# SUPERPID.net
KiCad netlist of a schematic drawn in Altium Designer
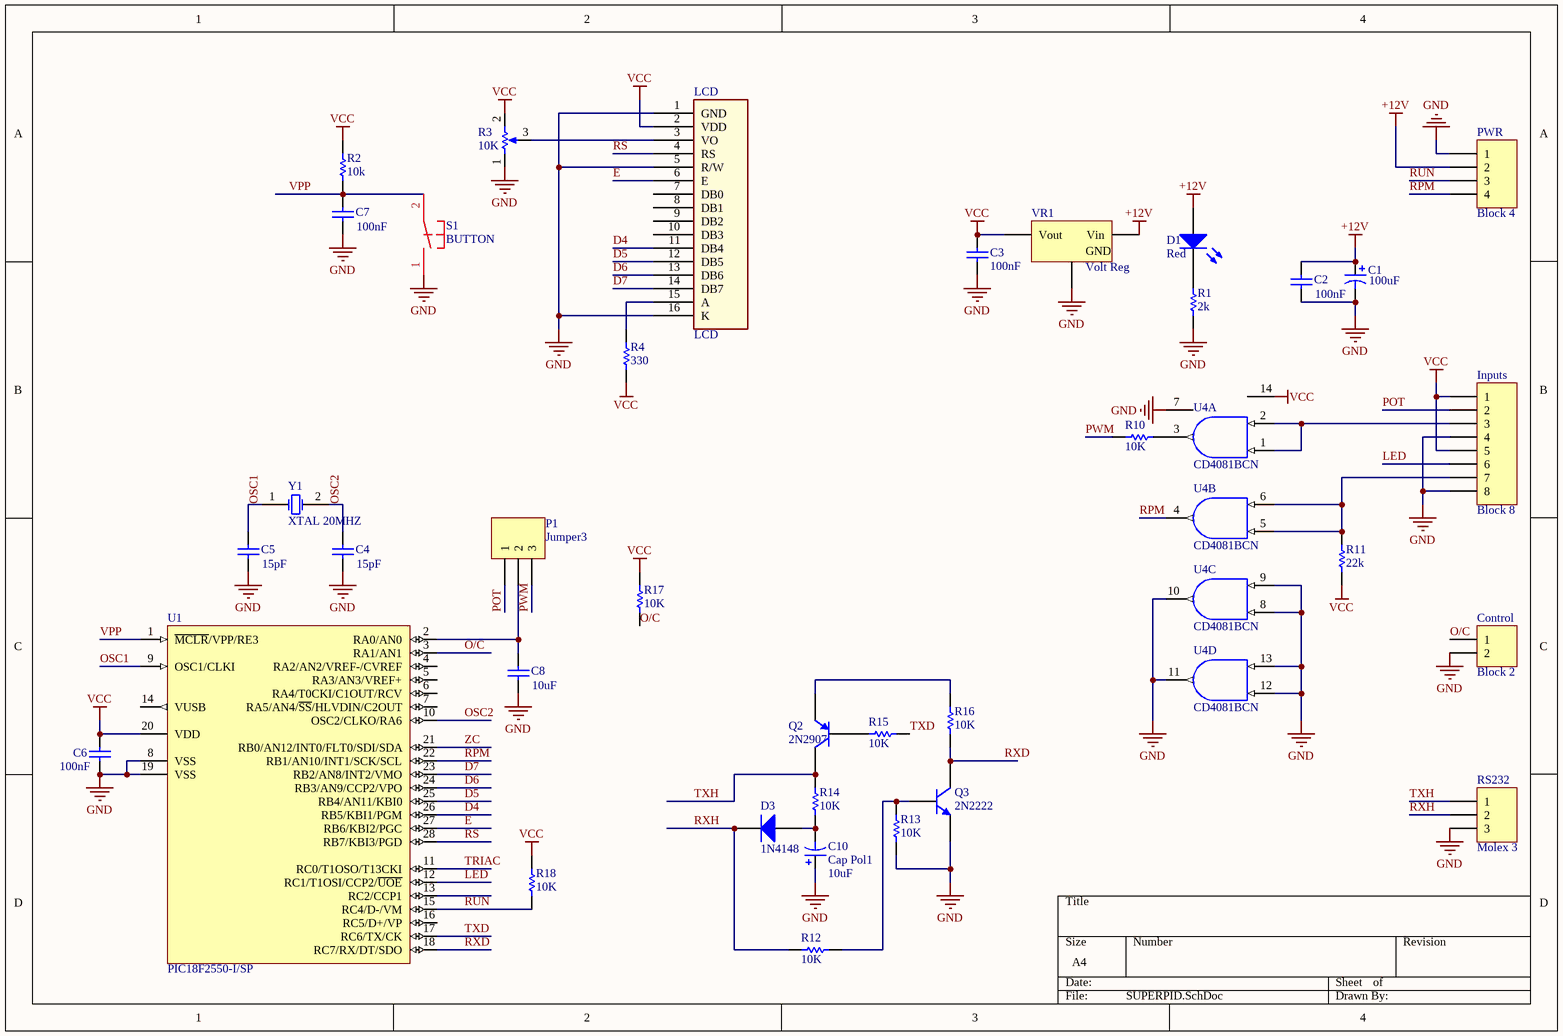
[diagram p0: SUPERPID.SchDoc]

(export (version "E")
  (design (tool "Eeschema 10.0.6"))
  (components
    (comp (ref "C1")
      (value "100uF")
      (footprint "RADIAL CAPACITOR - 100uF - 10V")
      (description "Polarized Capacitor (Radial)")
      (fields (field (name "PUBLISHER") "Altium Limited"))
      (libsource (lib "Miscellaneous Devices") (part "Cap Pol1"))
    )
    (comp (ref "C2")
      (value "100nF")
      (footprint "6-0805_N")
      (description "Capacitor 0805")
      (fields (field (name "PUBLISHER") "Altium Limited"))
      (libsource (lib "Miscellaneous Devices") (part "Cap Semi"))
    )
    (comp (ref "C3")
      (value "100nF")
      (footprint "6-0805_N")
      (description "Capacitor 0805")
      (fields (field (name "PUBLISHER") "Altium Limited"))
      (libsource (lib "Miscellaneous Devices") (part "Cap Semi"))
    )
    (comp (ref "C4")
      (value "15pF")
      (footprint "6-0805_N")
      (description "Capacitor 0805")
      (fields (field (name "PUBLISHER") "Altium Limited"))
      (libsource (lib "Miscellaneous Devices") (part "Cap Semi"))
    )
    (comp (ref "C5")
      (value "15pF")
      (footprint "6-0805_N")
      (description "Capacitor 0805")
      (fields (field (name "PUBLISHER") "Altium Limited"))
      (libsource (lib "Miscellaneous Devices") (part "Cap Semi"))
    )
    (comp (ref "C6")
      (value "100nF")
      (footprint "6-0805_N")
      (description "Capacitor 0805")
      (fields (field (name "PUBLISHER") "Altium Limited"))
      (libsource (lib "Miscellaneous Devices") (part "Cap Semi"))
    )
    (comp (ref "C7")
      (value "100nF")
      (footprint "6-0805_N")
      (description "Capacitor 0805")
      (fields (field (name "PUBLISHER") "Altium Limited"))
      (libsource (lib "Miscellaneous Devices") (part "Cap Semi"))
    )
    (comp (ref "C8")
      (value "10uF")
      (footprint "CC3216-1206")
      (description "Capacitor 0805")
      (fields (field (name "PUBLISHER") "Altium Limited"))
      (libsource (lib "Miscellaneous Devices") (part "Cap Semi"))
    )
    (comp (ref "C10")
      (value "Cap Pol1")
      (footprint "CONDENSADOR SMT")
      (description "Polarized Capacitor (Radial)")
      (fields (field (name "ALTIUM_VALUE") "10uF"))
      (libsource (lib "Miscellaneous Devices") (part "Cap Pol1"))
    )
    (comp (ref "Control")
      (value "Block 2")
      (footprint "BOR-2")
      (description "Header, 2-Pin")
      (fields (field (name "PUBLISHER") "Altium Limited"))
      (libsource (lib "Miscellaneous Connectors") (part "Header 2"))
    )
    (comp (ref "D1")
      (value "Red")
      (footprint "0805 LED RED")
      (description "Typical BLUE SiC LED")
      (fields (field (name "PUBLISHER") "Altium Limited"))
      (libsource (lib "Miscellaneous Devices") (part "LED3"))
    )
    (comp (ref "D3")
      (value "1N4148")
      (footprint "Diodo")
      (description "1 Amp General Purpose Rectifier")
      (fields (field (name "PUBLISHER") "Altium Limited"))
      (libsource (lib "Miscellaneous Devices") (part "Diode 1N4007"))
    )
    (comp (ref "Inputs")
      (value "Block 8")
      (footprint "BOR-8-5.08")
      (description "Header, 8-Pin")
      (fields (field (name "PUBLISHER") "Altium Limited"))
      (libsource (lib "Miscellaneous Connectors") (part "Header 8"))
    )
    (comp (ref "LCD")
      (value "LCD")
      (footprint "LCD 16x2")
      (description "HD44780 parallel interface chipset")
      (libsource (lib "ESQUEMATICOS") (part "LCD 16*2"))
    )
    (comp (ref "P1")
      (value "Jumper3")
      (footprint "HDR1X3")
      (description "Header, 3-Pin")
      (fields (field (name "PUBLISHER") "Altium Limited"))
      (libsource (lib "Miscellaneous Connectors") (part "Header 3"))
    )
    (comp (ref "PWR")
      (value "Block 4")
      (footprint "BOR-4-5.08")
      (description "Header, 4-Pin")
      (fields (field (name "PUBLISHER") "Altium Limited"))
      (libsource (lib "Miscellaneous Connectors") (part "Header 4"))
    )
    (comp (ref "Q2")
      (value "2N2907")
      (footprint "SOT-23 - PNP")
      (description "PNP Bipolar Transistor")
      (fields (field (name "PUBLISHER") "Altium Limited"))
      (libsource (lib "Miscellaneous Devices") (part "PNP"))
    )
    (comp (ref "Q3")
      (value "2N2222")
      (footprint "SOT-23")
      (description "NPN Bipolar Transistor")
      (fields (field (name "PUBLISHER") "Altium Limited"))
      (libsource (lib "Miscellaneous Devices") (part "NPN"))
    )
    (comp (ref "R1")
      (value "2k")
      (footprint "6-0805_M")
      (description "Chip Resistor 1206")
      (fields (field (name "PUBLISHER") "Altium Limited"))
      (libsource (lib "Miscellaneous Devices") (part "Res1"))
    )
    (comp (ref "R2")
      (value "10k")
      (footprint "6-0805_M")
      (description "Chip Resistor 1206")
      (fields (field (name "PUBLISHER") "Altium Limited"))
      (libsource (lib "Miscellaneous Devices") (part "Res1"))
    )
    (comp (ref "R3")
      (value "10K")
      (footprint "TrimPot")
      (description "Potentiometer")
      (fields (field (name "PUBLISHER") "Altium Limited"))
      (libsource (lib "Miscellaneous Devices") (part "RPot"))
    )
    (comp (ref "R4")
      (value "330")
      (footprint "CR3216-1206")
      (description "Chip Resistor 1206")
      (fields (field (name "Comment") "330R") (field (name "PUBLISHER") "Altium Limited"))
      (libsource (lib "Miscellaneous Devices") (part "Res1"))
    )
    (comp (ref "R10")
      (value "10K")
      (footprint "6-0805_N")
      (description "Resistor")
      (libsource (lib "Miscellaneous Devices") (part "Res1"))
    )
    (comp (ref "R11")
      (value "22k")
      (footprint "CR3216-1206")
      (description "Resistor")
      (libsource (lib "Miscellaneous Devices") (part "Res1"))
    )
    (comp (ref "R12")
      (value "10K")
      (footprint "CR3216-1206")
      (description "Resistor")
      (libsource (lib "Miscellaneous Devices") (part "Res1"))
    )
    (comp (ref "R13")
      (value "10K")
      (footprint "CR3216-1206")
      (description "Resistor")
      (libsource (lib "Miscellaneous Devices") (part "Res1"))
    )
    (comp (ref "R14")
      (value "10K")
      (footprint "CR3216-1206")
      (description "Resistor")
      (libsource (lib "Miscellaneous Devices") (part "Res1"))
    )
    (comp (ref "R15")
      (value "10K")
      (footprint "CR3216-1206")
      (description "Resistor")
      (libsource (lib "Miscellaneous Devices") (part "Res1"))
    )
    (comp (ref "R16")
      (value "10K")
      (footprint "CR3216-1206")
      (description "Resistor")
      (libsource (lib "Miscellaneous Devices") (part "Res1"))
    )
    (comp (ref "R17")
      (value "10K")
      (footprint "CR3216-1206")
      (description "Resistor")
      (libsource (lib "Miscellaneous Devices") (part "Res1"))
    )
    (comp (ref "R18")
      (value "10K")
      (footprint "CR3216-1206")
      (description "Resistor")
      (libsource (lib "Miscellaneous Devices") (part "Res1"))
    )
    (comp (ref "RS232")
      (value "Molex 3")
      (footprint "BOR-3")
      (description "Header, 3-Pin")
      (fields (field (name "PUBLISHER") "Altium Limited"))
      (libsource (lib "") (part "Header 3_1"))
    )
    (comp (ref "S1")
      (value "BUTTON")
      (footprint "Switch - Omron")
      (libsource (lib "ESQUEMATICOS") (part "BUTTON"))
    )
    (comp (ref "U1")
      (value "PIC18F2550-I/SP")
      (footprint "SPDIP300-SP28")
      (fields (field (name "PUBLISHER") "Altium Limited"))
      (libsource (lib "Microchip Microcontroller 8-Bit PIC18") (part "PIC18F2550-I/SP"))
    )
    (comp (ref "U4")
      (value "CD4081BCN")
      (footprint "N14A")
      (description "Quad 2-Input AND Buffered B series Gate, 14-Pin PDIP")
      (fields (field (name "PUBLISHER") "Altium Limited"))
      (libsource (lib "FSC Logic Gate") (part "CD4081BCN"))
    )
    (comp (ref "VR1")
      (value "Volt Reg")
      (footprint "TO263-3-TD")
      (description "Voltage Regulator")
      (fields (field (name "PUBLISHER") "Altium Limited"))
      (libsource (lib "Miscellaneous Devices") (part "Volt Reg"))
    )
    (comp (ref "Y1")
      (value "XTAL 20MHZ")
      (footprint "XTAL-2")
      (description "Crystal Oscillator")
      (fields (field (name "PUBLISHER") "Altium Limited"))
      (libsource (lib "Miscellaneous Devices") (part "XTAL"))
    )
  )
  (nets
    (net (code "1") (name "+12V") (class "Default")
      (node (ref "C1") (pin "1") (pinfunction "1_1") (pintype "passive"))
      (node (ref "C2") (pin "1") (pinfunction "1_1") (pintype "passive"))
      (node (ref "D1") (pin "1") (pinfunction "A_1") (pintype "passive"))
      (node (ref "PWR") (pin "2") (pinfunction "2_2") (pintype "passive"))
      (node (ref "VR1") (pin "1") (pinfunction "Vin_1") (pintype "passive"))
    )
    (net (code "2") (name "/D4") (class "Default")
      (node (ref "LCD") (pin "11") (pinfunction "DB4_11") (pintype "passive"))
      (node (ref "U1") (pin "26") (pinfunction "RB5/KBI1/PGM_26") (pintype "bidirectional"))
    )
    (net (code "3") (name "/D5") (class "Default")
      (node (ref "LCD") (pin "12") (pinfunction "DB5_12") (pintype "passive"))
      (node (ref "U1") (pin "25") (pinfunction "RB4/AN11/KBI0_25") (pintype "bidirectional"))
    )
    (net (code "4") (name "/D6") (class "Default")
      (node (ref "LCD") (pin "13") (pinfunction "DB6_13") (pintype "passive"))
      (node (ref "U1") (pin "24") (pinfunction "RB3/AN9/CCP2/VPO_24") (pintype "bidirectional"))
    )
    (net (code "5") (name "/D7") (class "Default")
      (node (ref "LCD") (pin "14") (pinfunction "DB7_14") (pintype "passive"))
      (node (ref "U1") (pin "23") (pinfunction "RB2/AN8/INT2/VMO_23") (pintype "bidirectional"))
    )
    (net (code "6") (name "/E") (class "Default")
      (node (ref "LCD") (pin "6") (pinfunction "E_6") (pintype "passive"))
      (node (ref "U1") (pin "27") (pinfunction "RB6/KBI2/PGC_27") (pintype "bidirectional"))
    )
    (net (code "7") (name "/LED") (class "Default")
      (node (ref "Inputs") (pin "6") (pinfunction "6_6") (pintype "passive"))
      (node (ref "U1") (pin "12") (pinfunction "RC1/T1OSI/CCP2/~{UOE}_12") (pintype "bidirectional"))
    )
    (net (code "8") (name "/OSC1") (class "Default")
      (node (ref "C5") (pin "1") (pinfunction "1_1") (pintype "passive"))
      (node (ref "U1") (pin "9") (pinfunction "OSC1/CLKI_9") (pintype "input"))
      (node (ref "Y1") (pin "1") (pinfunction "OSC1_1") (pintype "passive"))
    )
    (net (code "9") (name "/OSC2") (class "Default")
      (node (ref "C4") (pin "1") (pinfunction "1_1") (pintype "passive"))
      (node (ref "U1") (pin "10") (pinfunction "OSC2/CLKO/RA6_10") (pintype "bidirectional"))
      (node (ref "Y1") (pin "2") (pinfunction "OSC2_2") (pintype "passive"))
    )
    (net (code "10") (name "/O{slash}C") (class "Default")
      (node (ref "Control") (pin "1") (pinfunction "1_1") (pintype "passive"))
      (node (ref "R17") (pin "1") (pinfunction "1_1") (pintype "passive"))
      (node (ref "U1") (pin "3") (pinfunction "RA1/AN1_3") (pintype "bidirectional"))
    )
    (net (code "11") (name "/POT") (class "Default")
      (node (ref "Inputs") (pin "2") (pinfunction "2_2") (pintype "passive"))
      (node (ref "P1") (pin "1") (pinfunction "1_1") (pintype "passive"))
    )
    (net (code "12") (name "/PWM") (class "Default")
      (node (ref "P1") (pin "3") (pinfunction "3_3") (pintype "passive"))
      (node (ref "R10") (pin "2") (pinfunction "2_2") (pintype "passive"))
    )
    (net (code "13") (name "/RPM") (class "Default")
      (node (ref "PWR") (pin "4") (pinfunction "4_4") (pintype "passive"))
      (node (ref "U1") (pin "22") (pinfunction "RB1/AN10/INT1/SCK/SCL_22") (pintype "bidirectional"))
      (node (ref "U4") (pin "4") (pinfunction "J_4") (pintype "output"))
    )
    (net (code "14") (name "/RS") (class "Default")
      (node (ref "LCD") (pin "4") (pinfunction "RS_4") (pintype "passive"))
      (node (ref "U1") (pin "28") (pinfunction "RB7/KBI3/PGD_28") (pintype "bidirectional"))
    )
    (net (code "15") (name "/RUN") (class "Default")
      (node (ref "PWR") (pin "3") (pinfunction "3_3") (pintype "passive"))
      (node (ref "R18") (pin "1") (pinfunction "1_1") (pintype "passive"))
      (node (ref "U1") (pin "15") (pinfunction "RC4/D-/VM_15") (pintype "bidirectional"))
    )
    (net (code "16") (name "/RXD") (class "Default")
      (node (ref "Q3") (pin "C") (pinfunction "C_C") (pintype "passive"))
      (node (ref "R16") (pin "1") (pinfunction "1_1") (pintype "passive"))
      (node (ref "U1") (pin "18") (pinfunction "RC7/RX/DT/SDO_18") (pintype "bidirectional"))
    )
    (net (code "17") (name "/RXH") (class "Default")
      (node (ref "D3") (pin "2") (pinfunction "K_2") (pintype "passive"))
      (node (ref "R12") (pin "2") (pinfunction "2_2") (pintype "passive"))
      (node (ref "RS232") (pin "2") (pinfunction "2_2") (pintype "passive"))
    )
    (net (code "18") (name "/TRIAC") (class "Default")
      (node (ref "U1") (pin "11") (pinfunction "RC0/T1OSO/T13CKI_11") (pintype "bidirectional"))
    )
    (net (code "19") (name "/TXD") (class "Default")
      (node (ref "R15") (pin "2") (pinfunction "2_2") (pintype "passive"))
      (node (ref "U1") (pin "17") (pinfunction "RC6/TX/CK_17") (pintype "bidirectional"))
    )
    (net (code "20") (name "/TXH") (class "Default")
      (node (ref "Q2") (pin "C") (pinfunction "C_C") (pintype "passive"))
      (node (ref "R14") (pin "1") (pinfunction "1_1") (pintype "passive"))
      (node (ref "RS232") (pin "1") (pinfunction "1_1") (pintype "passive"))
    )
    (net (code "21") (name "/VPP") (class "Default")
      (node (ref "C7") (pin "1") (pinfunction "1_1") (pintype "passive"))
      (node (ref "R2") (pin "1") (pinfunction "1_1") (pintype "passive"))
      (node (ref "S1") (pin "2") (pinfunction "2_2") (pintype "passive"))
      (node (ref "U1") (pin "1") (pinfunction "~{MCLR}/VPP/RE3_1") (pintype "input"))
    )
    (net (code "22") (name "/ZC") (class "Default")
      (node (ref "U1") (pin "21") (pinfunction "RB0/AN12/INT0/FLT0/SDI/SDA_21") (pintype "bidirectional"))
    )
    (net (code "23") (name "GND") (class "Default")
      (node (ref "C1") (pin "2") (pinfunction "2_2") (pintype "passive"))
      (node (ref "C10") (pin "1") (pinfunction "1_1") (pintype "passive"))
      (node (ref "C2") (pin "2") (pinfunction "2_2") (pintype "passive"))
      (node (ref "C3") (pin "1") (pinfunction "1_1") (pintype "passive"))
      (node (ref "C4") (pin "2") (pinfunction "2_2") (pintype "passive"))
      (node (ref "C5") (pin "2") (pinfunction "2_2") (pintype "passive"))
      (node (ref "C6") (pin "2") (pinfunction "2_2") (pintype "passive"))
      (node (ref "C7") (pin "2") (pinfunction "2_2") (pintype "passive"))
      (node (ref "C8") (pin "2") (pinfunction "2_2") (pintype "passive"))
      (node (ref "Control") (pin "2") (pinfunction "2_2") (pintype "passive"))
      (node (ref "Inputs") (pin "4") (pinfunction "4_4") (pintype "passive"))
      (node (ref "Inputs") (pin "8") (pinfunction "8_8") (pintype "passive"))
      (node (ref "LCD") (pin "1") (pinfunction "GND_1") (pintype "passive"))
      (node (ref "LCD") (pin "16") (pinfunction "K_16") (pintype "passive"))
      (node (ref "LCD") (pin "5") (pinfunction "R/W_5") (pintype "passive"))
      (node (ref "PWR") (pin "1") (pinfunction "1_1") (pintype "passive"))
      (node (ref "Q3") (pin "E") (pinfunction "E_E") (pintype "passive"))
      (node (ref "R1") (pin "1") (pinfunction "1_1") (pintype "passive"))
      (node (ref "R13") (pin "2") (pinfunction "2_2") (pintype "passive"))
      (node (ref "R3") (pin "1") (pinfunction "TOP_1") (pintype "passive"))
      (node (ref "RS232") (pin "3") (pinfunction "3_3") (pintype "passive"))
      (node (ref "S1") (pin "1") (pinfunction "1_1") (pintype "passive"))
      (node (ref "U1") (pin "19") (pinfunction "VSS_19") (pintype "power_in"))
      (node (ref "U1") (pin "8") (pinfunction "VSS_8") (pintype "power_in"))
      (node (ref "U4") (pin "10") (pinfunction "J_10") (pintype "output"))
      (node (ref "U4") (pin "11") (pinfunction "J_11") (pintype "output"))
      (node (ref "U4") (pin "12") (pinfunction "A_12") (pintype "input"))
      (node (ref "U4") (pin "13") (pinfunction "B_13") (pintype "input"))
      (node (ref "U4") (pin "7") (pinfunction "GND_7") (pintype "power_in"))
      (node (ref "U4") (pin "8") (pinfunction "A_8") (pintype "input"))
      (node (ref "U4") (pin "9") (pinfunction "B_9") (pintype "input"))
      (node (ref "VR1") (pin "2") (pinfunction "GND_2") (pintype "passive"))
    )
    (net (code "24") (name "Net-(D1-K)") (class "Default")
      (node (ref "D1") (pin "2") (pinfunction "K_2") (pintype "passive"))
      (node (ref "R1") (pin "2") (pinfunction "2_2") (pintype "passive"))
    )
    (net (code "25") (name "Net-(D3-A)") (class "Default")
      (node (ref "C10") (pin "2") (pinfunction "2_2") (pintype "passive"))
      (node (ref "D3") (pin "1") (pinfunction "A_1") (pintype "passive"))
      (node (ref "R14") (pin "2") (pinfunction "2_2") (pintype "passive"))
    )
    (net (code "26") (name "Net-(LCD-A)") (class "Default")
      (node (ref "LCD") (pin "15") (pinfunction "A_15") (pintype "passive"))
      (node (ref "R4") (pin "1") (pinfunction "1_1") (pintype "passive"))
    )
    (net (code "27") (name "Net-(LCD-VO)") (class "Default")
      (node (ref "LCD") (pin "3") (pinfunction "VO_3") (pintype "passive"))
      (node (ref "R3") (pin "3") (pinfunction "TAP_3") (pintype "passive"))
    )
    (net (code "28") (name "Net-(Q2-PadB)") (class "Default")
      (node (ref "Q2") (pin "B") (pinfunction "B_B") (pintype "passive"))
      (node (ref "R15") (pin "1") (pinfunction "1_1") (pintype "passive"))
    )
    (net (code "29") (name "Net-(Q2-PadE)") (class "Default")
      (node (ref "Q2") (pin "E") (pinfunction "E_E") (pintype "passive"))
      (node (ref "R16") (pin "2") (pinfunction "2_2") (pintype "passive"))
    )
    (net (code "30") (name "Net-(Q3-PadB)") (class "Default")
      (node (ref "Q3") (pin "B") (pinfunction "B_B") (pintype "passive"))
      (node (ref "R12") (pin "1") (pinfunction "1_1") (pintype "passive"))
      (node (ref "R13") (pin "1") (pinfunction "1_1") (pintype "passive"))
    )
    (net (code "31") (name "Net-(U1-RA0{slash}AN0)") (class "Default")
      (node (ref "C8") (pin "1") (pinfunction "1_1") (pintype "passive"))
      (node (ref "P1") (pin "2") (pinfunction "2_2") (pintype "passive"))
      (node (ref "U1") (pin "2") (pinfunction "RA0/AN0_2") (pintype "bidirectional"))
    )
    (net (code "32") (name "Net-(U4A-A)") (class "Default")
      (node (ref "Inputs") (pin "3") (pinfunction "3_3") (pintype "passive"))
      (node (ref "U4") (pin "1") (pinfunction "A_1") (pintype "input"))
      (node (ref "U4") (pin "2") (pinfunction "B_2") (pintype "input"))
    )
    (net (code "33") (name "Net-(U4A-J)") (class "Default")
      (node (ref "R10") (pin "1") (pinfunction "1_1") (pintype "passive"))
      (node (ref "U4") (pin "3") (pinfunction "J_3") (pintype "output"))
    )
    (net (code "34") (name "Net-(U4B-A)") (class "Default")
      (node (ref "Inputs") (pin "7") (pinfunction "7_7") (pintype "passive"))
      (node (ref "R11") (pin "2") (pinfunction "2_2") (pintype "passive"))
      (node (ref "U4") (pin "5") (pinfunction "A_5") (pintype "input"))
      (node (ref "U4") (pin "6") (pinfunction "B_6") (pintype "input"))
    )
    (net (code "35") (name "VCC") (class "Default")
      (node (ref "C3") (pin "2") (pinfunction "2_2") (pintype "passive"))
      (node (ref "C6") (pin "1") (pinfunction "1_1") (pintype "passive"))
      (node (ref "Inputs") (pin "1") (pinfunction "1_1") (pintype "passive"))
      (node (ref "Inputs") (pin "5") (pinfunction "5_5") (pintype "passive"))
      (node (ref "LCD") (pin "2") (pinfunction "VDD_2") (pintype "passive"))
      (node (ref "R11") (pin "1") (pinfunction "1_1") (pintype "passive"))
      (node (ref "R17") (pin "2") (pinfunction "2_2") (pintype "passive"))
      (node (ref "R18") (pin "2") (pinfunction "2_2") (pintype "passive"))
      (node (ref "R2") (pin "2") (pinfunction "2_2") (pintype "passive"))
      (node (ref "R3") (pin "2") (pinfunction "BOT_2") (pintype "passive"))
      (node (ref "R4") (pin "2") (pinfunction "2_2") (pintype "passive"))
      (node (ref "U1") (pin "20") (pinfunction "VDD_20") (pintype "power_in"))
      (node (ref "U4") (pin "14") (pinfunction "VDD_14") (pintype "power_in"))
      (node (ref "VR1") (pin "3") (pinfunction "Vout_3") (pintype "passive"))
    )
    (net (code "36") (name "unconnected-(LCD-DB0-Pad7)") (class "Default")
      (node (ref "LCD") (pin "7") (pinfunction "DB0_7") (pintype "passive"))
    )
    (net (code "37") (name "unconnected-(LCD-DB1-Pad8)") (class "Default")
      (node (ref "LCD") (pin "8") (pinfunction "DB1_8") (pintype "passive"))
    )
    (net (code "38") (name "unconnected-(LCD-DB2-Pad9)") (class "Default")
      (node (ref "LCD") (pin "9") (pinfunction "DB2_9") (pintype "passive"))
    )
    (net (code "39") (name "unconnected-(LCD-DB3-Pad10)") (class "Default")
      (node (ref "LCD") (pin "10") (pinfunction "DB3_10") (pintype "passive"))
    )
    (net (code "40") (name "unconnected-(U1-RA2{slash}AN2{slash}VREF-{slash}CVREF-Pad4)") (class "Default")
      (node (ref "U1") (pin "4") (pinfunction "RA2/AN2/VREF-/CVREF_4") (pintype "bidirectional"))
    )
    (net (code "41") (name "unconnected-(U1-RA3{slash}AN3{slash}VREF+-Pad5)") (class "Default")
      (node (ref "U1") (pin "5") (pinfunction "RA3/AN3/VREF+_5") (pintype "bidirectional"))
    )
    (net (code "42") (name "unconnected-(U1-RA4{slash}T0CKI{slash}C1OUT{slash}RCV-Pad6)") (class "Default")
      (node (ref "U1") (pin "6") (pinfunction "RA4/T0CKI/C1OUT/RCV_6") (pintype "bidirectional"))
    )
    (net (code "43") (name "unconnected-(U1-RA5{slash}AN4{slash}~{SS}{slash}HLVDIN{slash}C2OUT-Pad7)") (class "Default")
      (node (ref "U1") (pin "7") (pinfunction "RA5/AN4/~{SS}/HLVDIN/C2OUT_7") (pintype "bidirectional"))
    )
    (net (code "44") (name "unconnected-(U1-RC2{slash}CCP1-Pad13)") (class "Default")
      (node (ref "U1") (pin "13") (pinfunction "RC2/CCP1_13") (pintype "bidirectional"))
    )
    (net (code "45") (name "unconnected-(U1-RC5{slash}D+{slash}VP-Pad16)") (class "Default")
      (node (ref "U1") (pin "16") (pinfunction "RC5/D+/VP_16") (pintype "bidirectional"))
    )
    (net (code "46") (name "unconnected-(U1-VUSB-Pad14)") (class "Default")
      (node (ref "U1") (pin "14") (pinfunction "VUSB_14") (pintype "output"))
    )
  )
)
